# main.net
KiCad netlist of a schematic drawn in Altium Designer
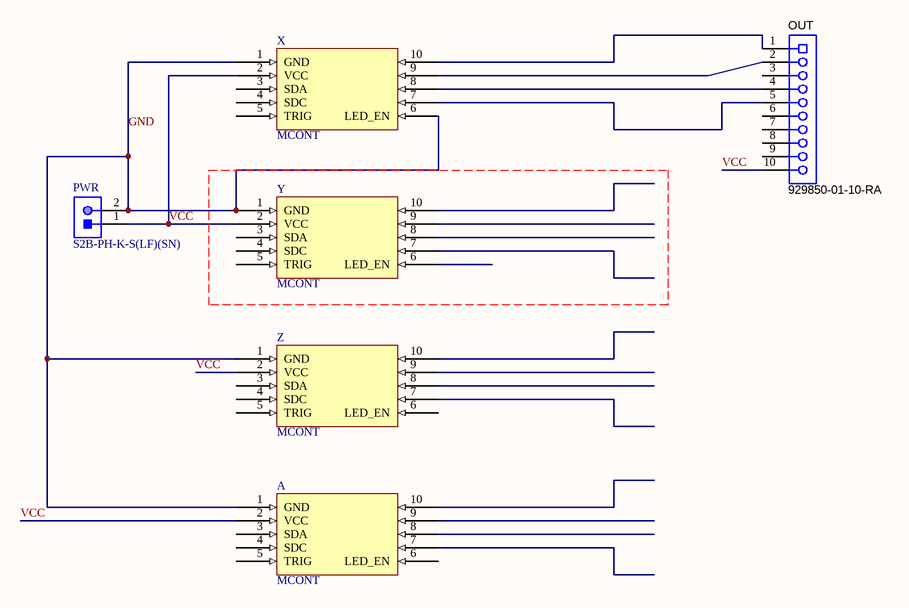
[diagram p0: main.SchDoc]

(export (version "E")
  (design (tool "Eeschema 10.0.6"))
  (components
    (comp (ref "A") (value "MCONT") (footprint "MCONT") (libsource (lib "fyshlib") (part "MCONT")))
    (comp (ref "OUT")
      (value "929850-01-10-RA")
      (footprint "3M-929850-01-10-RA_V")
      (fields (field (name "MANUFACTURER") "3M"))
      (libsource (lib "Cornell University") (part "CN-1P-F-R10"))
    )
    (comp (ref "PWR")
      (value "S2B-PH-K-S(LF)(SN)")
      (footprint "JST-S2B-PH-K-S_V")
      (fields (field (name "MANUFACTURER") "Japan Solderless Terminals"))
      (libsource (lib "Cornell University") (part "CN-1P-M-R2"))
    )
    (comp (ref "X") (value "MCONT") (footprint "MCONT") (libsource (lib "fyshlib") (part "MCONT")))
    (comp (ref "Y") (value "MCONT") (footprint "MCONT") (libsource (lib "fyshlib") (part "MCONT")))
    (comp (ref "Z") (value "MCONT") (footprint "MCONT") (libsource (lib "fyshlib") (part "MCONT")))
  )
  (nets
    (net (code "1") (name "/GND") (class "Default")
      (node (ref "A") (pin "1") (pinfunction "GND_1") (pintype "input"))
      (node (ref "PWR") (pin "2") (pinfunction "2_2") (pintype "passive"))
      (node (ref "X") (pin "1") (pinfunction "GND_1") (pintype "input"))
      (node (ref "X") (pin "6") (pinfunction "LED_EN_6") (pintype "input"))
      (node (ref "Y") (pin "1") (pinfunction "GND_1") (pintype "input"))
      (node (ref "Z") (pin "1") (pinfunction "GND_1") (pintype "input"))
    )
    (net (code "2") (name "/VCC") (class "Default")
      (node (ref "A") (pin "2") (pinfunction "VCC_2") (pintype "input"))
      (node (ref "OUT") (pin "10") (pinfunction "10_10") (pintype "passive"))
      (node (ref "PWR") (pin "1") (pinfunction "1_1") (pintype "passive"))
      (node (ref "X") (pin "2") (pinfunction "VCC_2") (pintype "input"))
      (node (ref "Y") (pin "2") (pinfunction "VCC_2") (pintype "input"))
      (node (ref "Z") (pin "2") (pinfunction "VCC_2") (pintype "input"))
    )
    (net (code "3") (name "Net-(OUT-Pad1)") (class "Default")
      (node (ref "OUT") (pin "1") (pinfunction "1_1") (pintype "passive"))
      (node (ref "X") (pin "10") (pintype "input"))
    )
    (net (code "4") (name "Net-(OUT-Pad2)") (class "Default")
      (node (ref "OUT") (pin "2") (pinfunction "2_2") (pintype "passive"))
      (node (ref "X") (pin "9") (pintype "input"))
    )
    (net (code "5") (name "Net-(OUT-Pad4)") (class "Default")
      (node (ref "OUT") (pin "4") (pinfunction "4_4") (pintype "passive"))
      (node (ref "X") (pin "8") (pintype "input"))
    )
    (net (code "6") (name "Net-(OUT-Pad5)") (class "Default")
      (node (ref "OUT") (pin "5") (pinfunction "5_5") (pintype "passive"))
      (node (ref "X") (pin "7") (pintype "input"))
    )
    (net (code "7") (name "unconnected-(A-LED_EN-Pad6)") (class "Default")
      (node (ref "A") (pin "6") (pinfunction "LED_EN_6") (pintype "input"))
    )
    (net (code "8") (name "unconnected-(A-Pad7)") (class "Default")
      (node (ref "A") (pin "7") (pintype "input"))
    )
    (net (code "9") (name "unconnected-(A-Pad8)") (class "Default")
      (node (ref "A") (pin "8") (pintype "input"))
    )
    (net (code "10") (name "unconnected-(A-Pad9)") (class "Default")
      (node (ref "A") (pin "9") (pintype "input"))
    )
    (net (code "11") (name "unconnected-(A-Pad10)") (class "Default")
      (node (ref "A") (pin "10") (pintype "input"))
    )
    (net (code "12") (name "unconnected-(A-SDA-Pad3)") (class "Default")
      (node (ref "A") (pin "3") (pinfunction "SDA_3") (pintype "input"))
    )
    (net (code "13") (name "unconnected-(A-SDC-Pad4)") (class "Default")
      (node (ref "A") (pin "4") (pinfunction "SDC_4") (pintype "input"))
    )
    (net (code "14") (name "unconnected-(A-TRIG-Pad5)") (class "Default")
      (node (ref "A") (pin "5") (pinfunction "TRIG_5") (pintype "input"))
    )
    (net (code "15") (name "unconnected-(OUT-Pad3)") (class "Default")
      (node (ref "OUT") (pin "3") (pinfunction "3_3") (pintype "passive"))
    )
    (net (code "16") (name "unconnected-(OUT-Pad6)") (class "Default")
      (node (ref "OUT") (pin "6") (pinfunction "6_6") (pintype "passive"))
    )
    (net (code "17") (name "unconnected-(OUT-Pad7)") (class "Default")
      (node (ref "OUT") (pin "7") (pinfunction "7_7") (pintype "passive"))
    )
    (net (code "18") (name "unconnected-(OUT-Pad8)") (class "Default")
      (node (ref "OUT") (pin "8") (pinfunction "8_8") (pintype "passive"))
    )
    (net (code "19") (name "unconnected-(OUT-Pad9)") (class "Default")
      (node (ref "OUT") (pin "9") (pinfunction "9_9") (pintype "passive"))
    )
    (net (code "20") (name "unconnected-(X-SDA-Pad3)") (class "Default")
      (node (ref "X") (pin "3") (pinfunction "SDA_3") (pintype "input"))
    )
    (net (code "21") (name "unconnected-(X-SDC-Pad4)") (class "Default")
      (node (ref "X") (pin "4") (pinfunction "SDC_4") (pintype "input"))
    )
    (net (code "22") (name "unconnected-(X-TRIG-Pad5)") (class "Default")
      (node (ref "X") (pin "5") (pinfunction "TRIG_5") (pintype "input"))
    )
    (net (code "23") (name "unconnected-(Y-LED_EN-Pad6)") (class "Default")
      (node (ref "Y") (pin "6") (pinfunction "LED_EN_6") (pintype "input"))
    )
    (net (code "24") (name "unconnected-(Y-Pad7)") (class "Default")
      (node (ref "Y") (pin "7") (pintype "input"))
    )
    (net (code "25") (name "unconnected-(Y-Pad8)") (class "Default")
      (node (ref "Y") (pin "8") (pintype "input"))
    )
    (net (code "26") (name "unconnected-(Y-Pad9)") (class "Default")
      (node (ref "Y") (pin "9") (pintype "input"))
    )
    (net (code "27") (name "unconnected-(Y-Pad10)") (class "Default")
      (node (ref "Y") (pin "10") (pintype "input"))
    )
    (net (code "28") (name "unconnected-(Y-SDA-Pad3)") (class "Default")
      (node (ref "Y") (pin "3") (pinfunction "SDA_3") (pintype "input"))
    )
    (net (code "29") (name "unconnected-(Y-SDC-Pad4)") (class "Default")
      (node (ref "Y") (pin "4") (pinfunction "SDC_4") (pintype "input"))
    )
    (net (code "30") (name "unconnected-(Y-TRIG-Pad5)") (class "Default")
      (node (ref "Y") (pin "5") (pinfunction "TRIG_5") (pintype "input"))
    )
    (net (code "31") (name "unconnected-(Z-LED_EN-Pad6)") (class "Default")
      (node (ref "Z") (pin "6") (pinfunction "LED_EN_6") (pintype "input"))
    )
    (net (code "32") (name "unconnected-(Z-Pad7)") (class "Default")
      (node (ref "Z") (pin "7") (pintype "input"))
    )
    (net (code "33") (name "unconnected-(Z-Pad8)") (class "Default")
      (node (ref "Z") (pin "8") (pintype "input"))
    )
    (net (code "34") (name "unconnected-(Z-Pad9)") (class "Default")
      (node (ref "Z") (pin "9") (pintype "input"))
    )
    (net (code "35") (name "unconnected-(Z-Pad10)") (class "Default")
      (node (ref "Z") (pin "10") (pintype "input"))
    )
    (net (code "36") (name "unconnected-(Z-SDA-Pad3)") (class "Default")
      (node (ref "Z") (pin "3") (pinfunction "SDA_3") (pintype "input"))
    )
    (net (code "37") (name "unconnected-(Z-SDC-Pad4)") (class "Default")
      (node (ref "Z") (pin "4") (pinfunction "SDC_4") (pintype "input"))
    )
    (net (code "38") (name "unconnected-(Z-TRIG-Pad5)") (class "Default")
      (node (ref "Z") (pin "5") (pinfunction "TRIG_5") (pintype "input"))
    )
  )
)
